# HW_Mechanical_Parts.net
KiCad netlist of a schematic drawn in Altium Designer
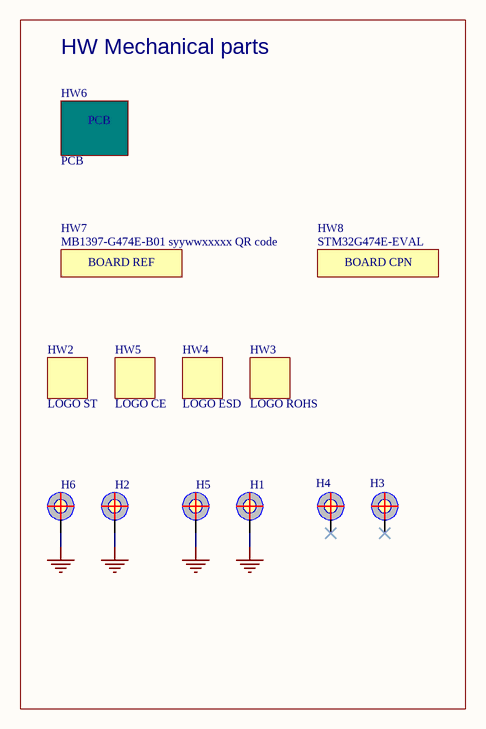
[diagram p0: HW_Mechanical_Parts.SchDoc]

(export (version "E")
  (design (tool "Eeschema 10.0.6"))
  (components
    (comp (ref "H1")
      (value "POSITION HOLE C7D3R5")
      (footprint "PTH_350_700")
      (fields (field (name "INTERNAL_PART_NUMBER") "MCD-00328"))
      (libsource (lib "MCD_PARTS_database") (part "POSITION HOLE C7D3R5"))
    )
    (comp (ref "H2")
      (value "POSITION HOLE C7D3R5")
      (footprint "PTH_350_700")
      (fields (field (name "INTERNAL_PART_NUMBER") "MCD-00328"))
      (libsource (lib "MCD_PARTS_database") (part "POSITION HOLE C7D3R5"))
    )
    (comp (ref "H3")
      (value "POSITION HOLE C3R5D3R5")
      (footprint "NPTH_350")
      (fields
        (field (name "INTERNAL_PART_NUMBER") "MCD-01368")
        (field (name "MANUFACTURER_PART_NUMBER") "n/a")
      )
      (libsource (lib "MCD_PARTS_database") (part "POSITION HOLE C3R5D3R5"))
    )
    (comp (ref "H4")
      (value "POSITION HOLE C3R5D3R5")
      (footprint "NPTH_350")
      (fields
        (field (name "INTERNAL_PART_NUMBER") "MCD-01368")
        (field (name "MANUFACTURER_PART_NUMBER") "n/a")
      )
      (libsource (lib "MCD_PARTS_database") (part "POSITION HOLE C3R5D3R5"))
    )
    (comp (ref "H5")
      (value "POSITION HOLE C7D3R5")
      (footprint "PTH_350_700")
      (fields (field (name "INTERNAL_PART_NUMBER") "MCD-00328"))
      (libsource (lib "MCD_PARTS_database") (part "POSITION HOLE C7D3R5"))
    )
    (comp (ref "H6")
      (value "POSITION HOLE C7D3R5")
      (footprint "PTH_350_700")
      (fields (field (name "INTERNAL_PART_NUMBER") "MCD-00328"))
      (libsource (lib "MCD_PARTS_database") (part "POSITION HOLE C7D3R5"))
    )
    (comp (ref "HW2")
      (value "LOGO ST")
      (footprint "LOGO_ST")
      (description "STMicroelectronics logo footprint for PCB")
      (fields
        (field (name "INTERNAL_PART_NUMBER") "MCD-00625")
        (field (name "MANUFACTURER_PART_NUMBER") "n/a")
      )
      (libsource (lib "MCD_PARTS_database") (part "Logo"))
    )
    (comp (ref "HW3")
      (value "LOGO ROHS")
      (footprint "LOGO_ROHS")
      (description "ROHS logo footprint for PCB")
      (fields (field (name "INTERNAL_PART_NUMBER") "MCD-00628") (field (name "Comment") "Logo"))
      (libsource (lib "MCD_PARTS_database") (part "Logo"))
    )
    (comp (ref "HW4")
      (value "LOGO ESD")
      (footprint "LOGO_MAIN_1")
      (description "Hand ESD logo footprint for PCB")
      (fields
        (field (name "INTERNAL_PART_NUMBER") "MCD-00627")
        (field (name "MANUFACTURER_PART_NUMBER") "n/a")
      )
      (libsource (lib "MCD_PARTS_database") (part "Logo"))
    )
    (comp (ref "HW5")
      (value "LOGO CE")
      (footprint "LOGO_CE")
      (description "CE logo footprint for PCB")
      (fields (field (name "INTERNAL_PART_NUMBER") "MCD-00626") (field (name "Comment") "Logo"))
      (libsource (lib "MCD_PARTS_database") (part "Logo"))
    )
    (comp (ref "HW6") (value "PCB") (libsource (lib "MCD_TEMP_NPA") (part "PCB")))
    (comp (ref "HW7")
      (value "MB1397-G474E-B01 syywwxxxxx QR code")
      (footprint "STICKER_25X9")
      (description "Sticker to mention board reference + serial number")
      (fields
        (field (name "INTERNAL_PART_NUMBER") "MCD-00235")
        (field (name "MANUFACTURER_PART_NUMBER") "n/a")
        (field (name "PROVIDED_BY") "SUBCO")
      )
      (libsource (lib "MCD_PARTS_database") (part "STICKER_BOARD_REF"))
    )
    (comp (ref "HW8")
      (value "STM32G474E-EVAL")
      (description "Sticker to mention board CPN code")
      (fields
        (field (name "INTERNAL_PART_NUMBER") "MCD-00549")
        (field (name "Comment") "STICKER_BOARD_CPN")
        (field (name "PROVIDED_BY") "Subcon")
      )
      (libsource (lib "MCD_PARTS_database") (part "STICKER_BOARD_CPN"))
    )
  )
  (nets
    (net (code "1") (name "GND") (class "Default")
      (node (ref "H1") (pin "1") (pinfunction "1_1") (pintype "passive"))
      (node (ref "H2") (pin "1") (pinfunction "1_1") (pintype "passive"))
      (node (ref "H5") (pin "1") (pinfunction "1_1") (pintype "passive"))
      (node (ref "H6") (pin "1") (pinfunction "1_1") (pintype "passive"))
    )
    (net (code "2") (name "unconnected-(H3-Pad1)") (class "Default")
      (node (ref "H3") (pin "1") (pinfunction "1_1") (pintype "passive+no_connect"))
    )
    (net (code "3") (name "unconnected-(H4-Pad1)") (class "Default")
      (node (ref "H4") (pin "1") (pinfunction "1_1") (pintype "passive+no_connect"))
    )
  )
)
